# Actuator-MKI-2.net
KiCad netlist of a schematic drawn in EAGLE
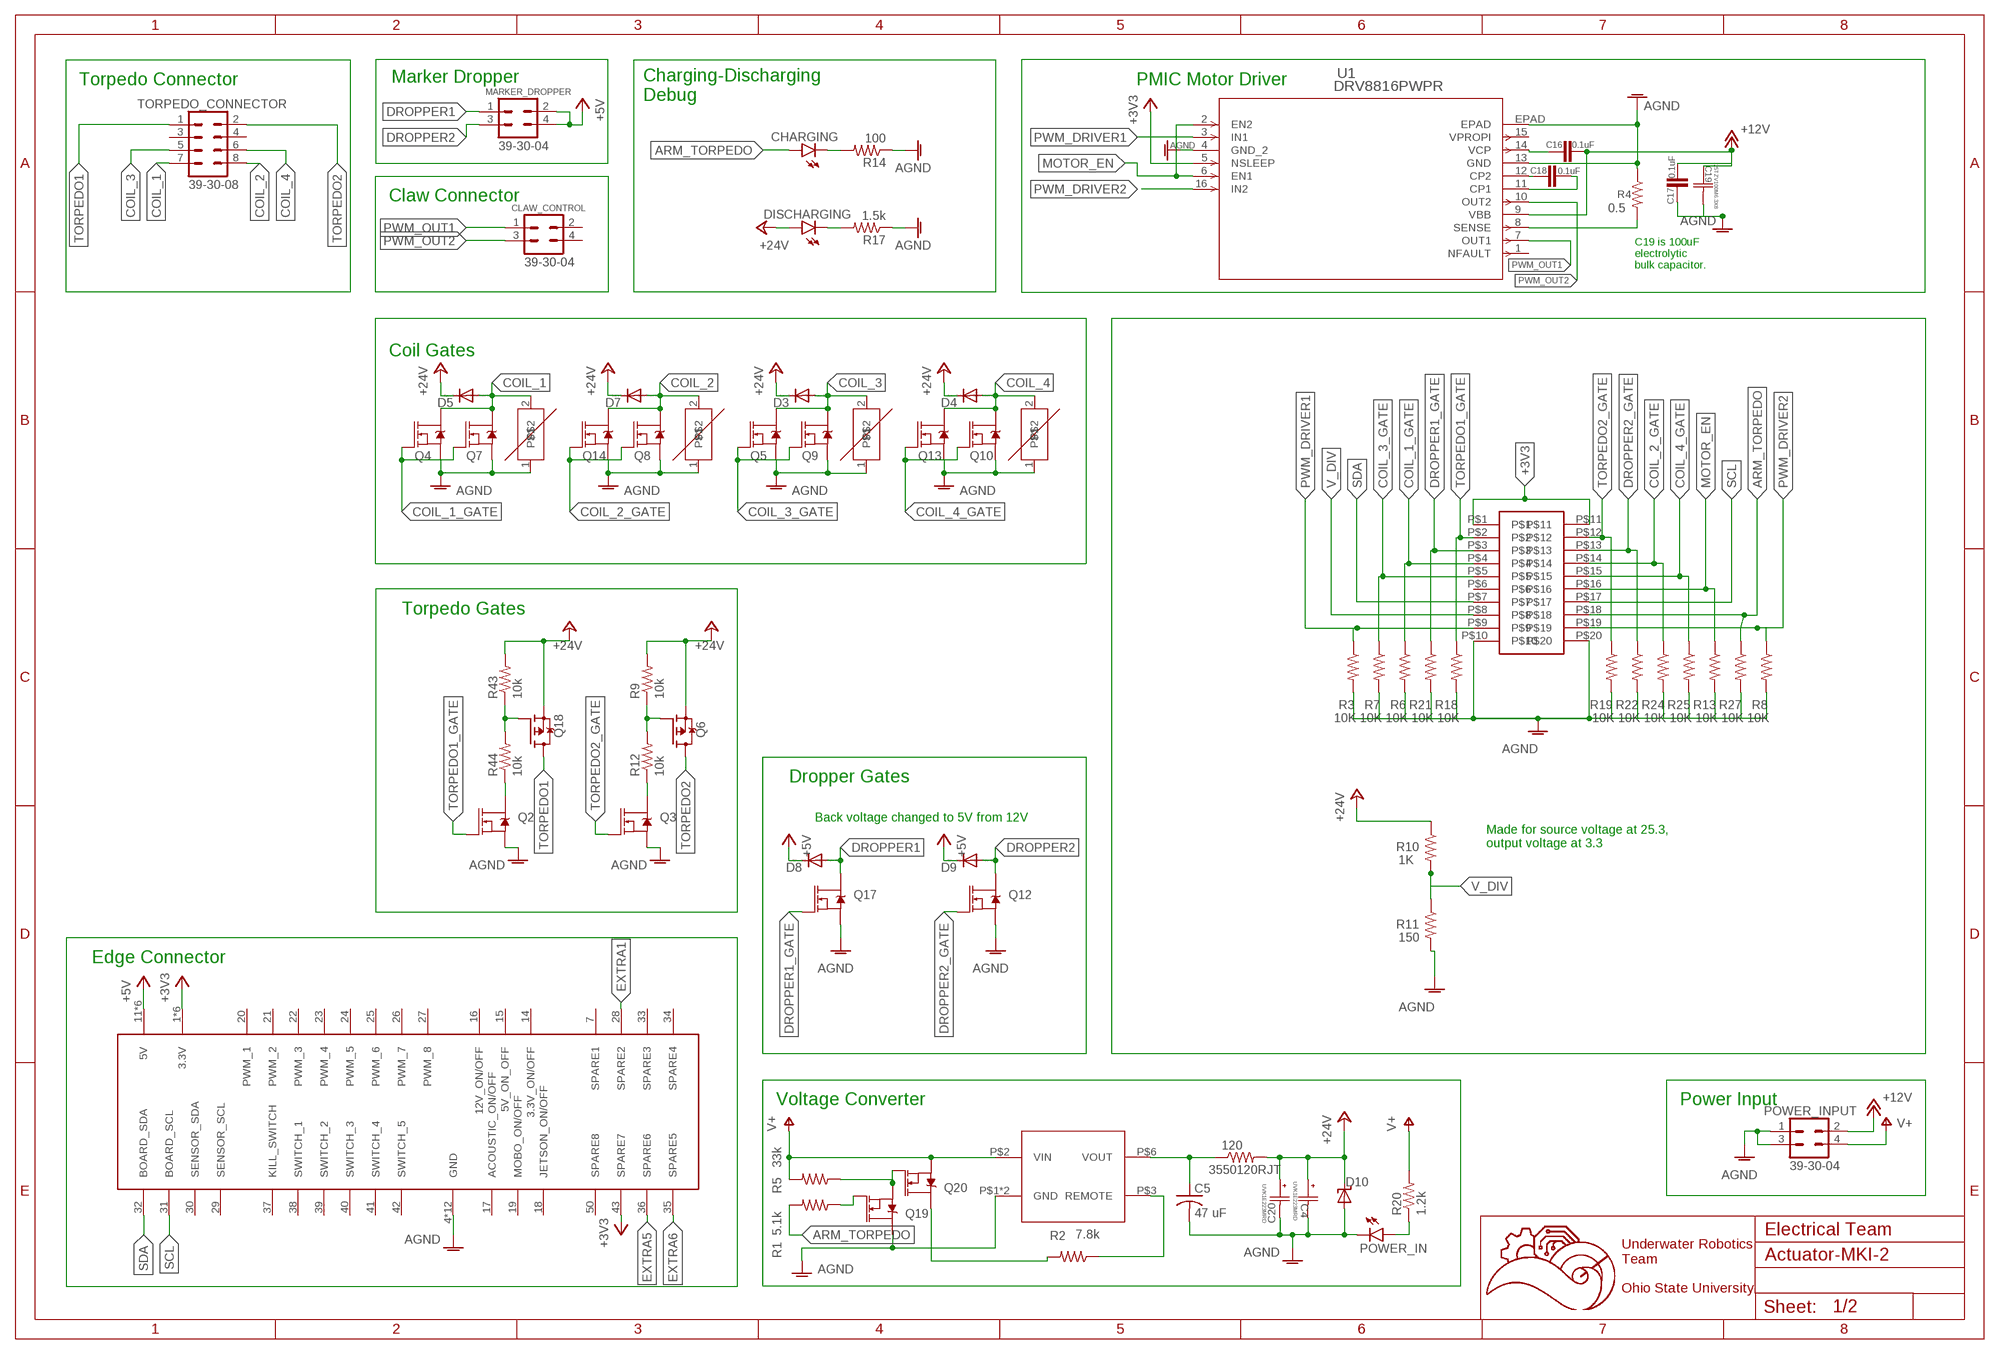
[diagram p0: schematic, sheet 1]
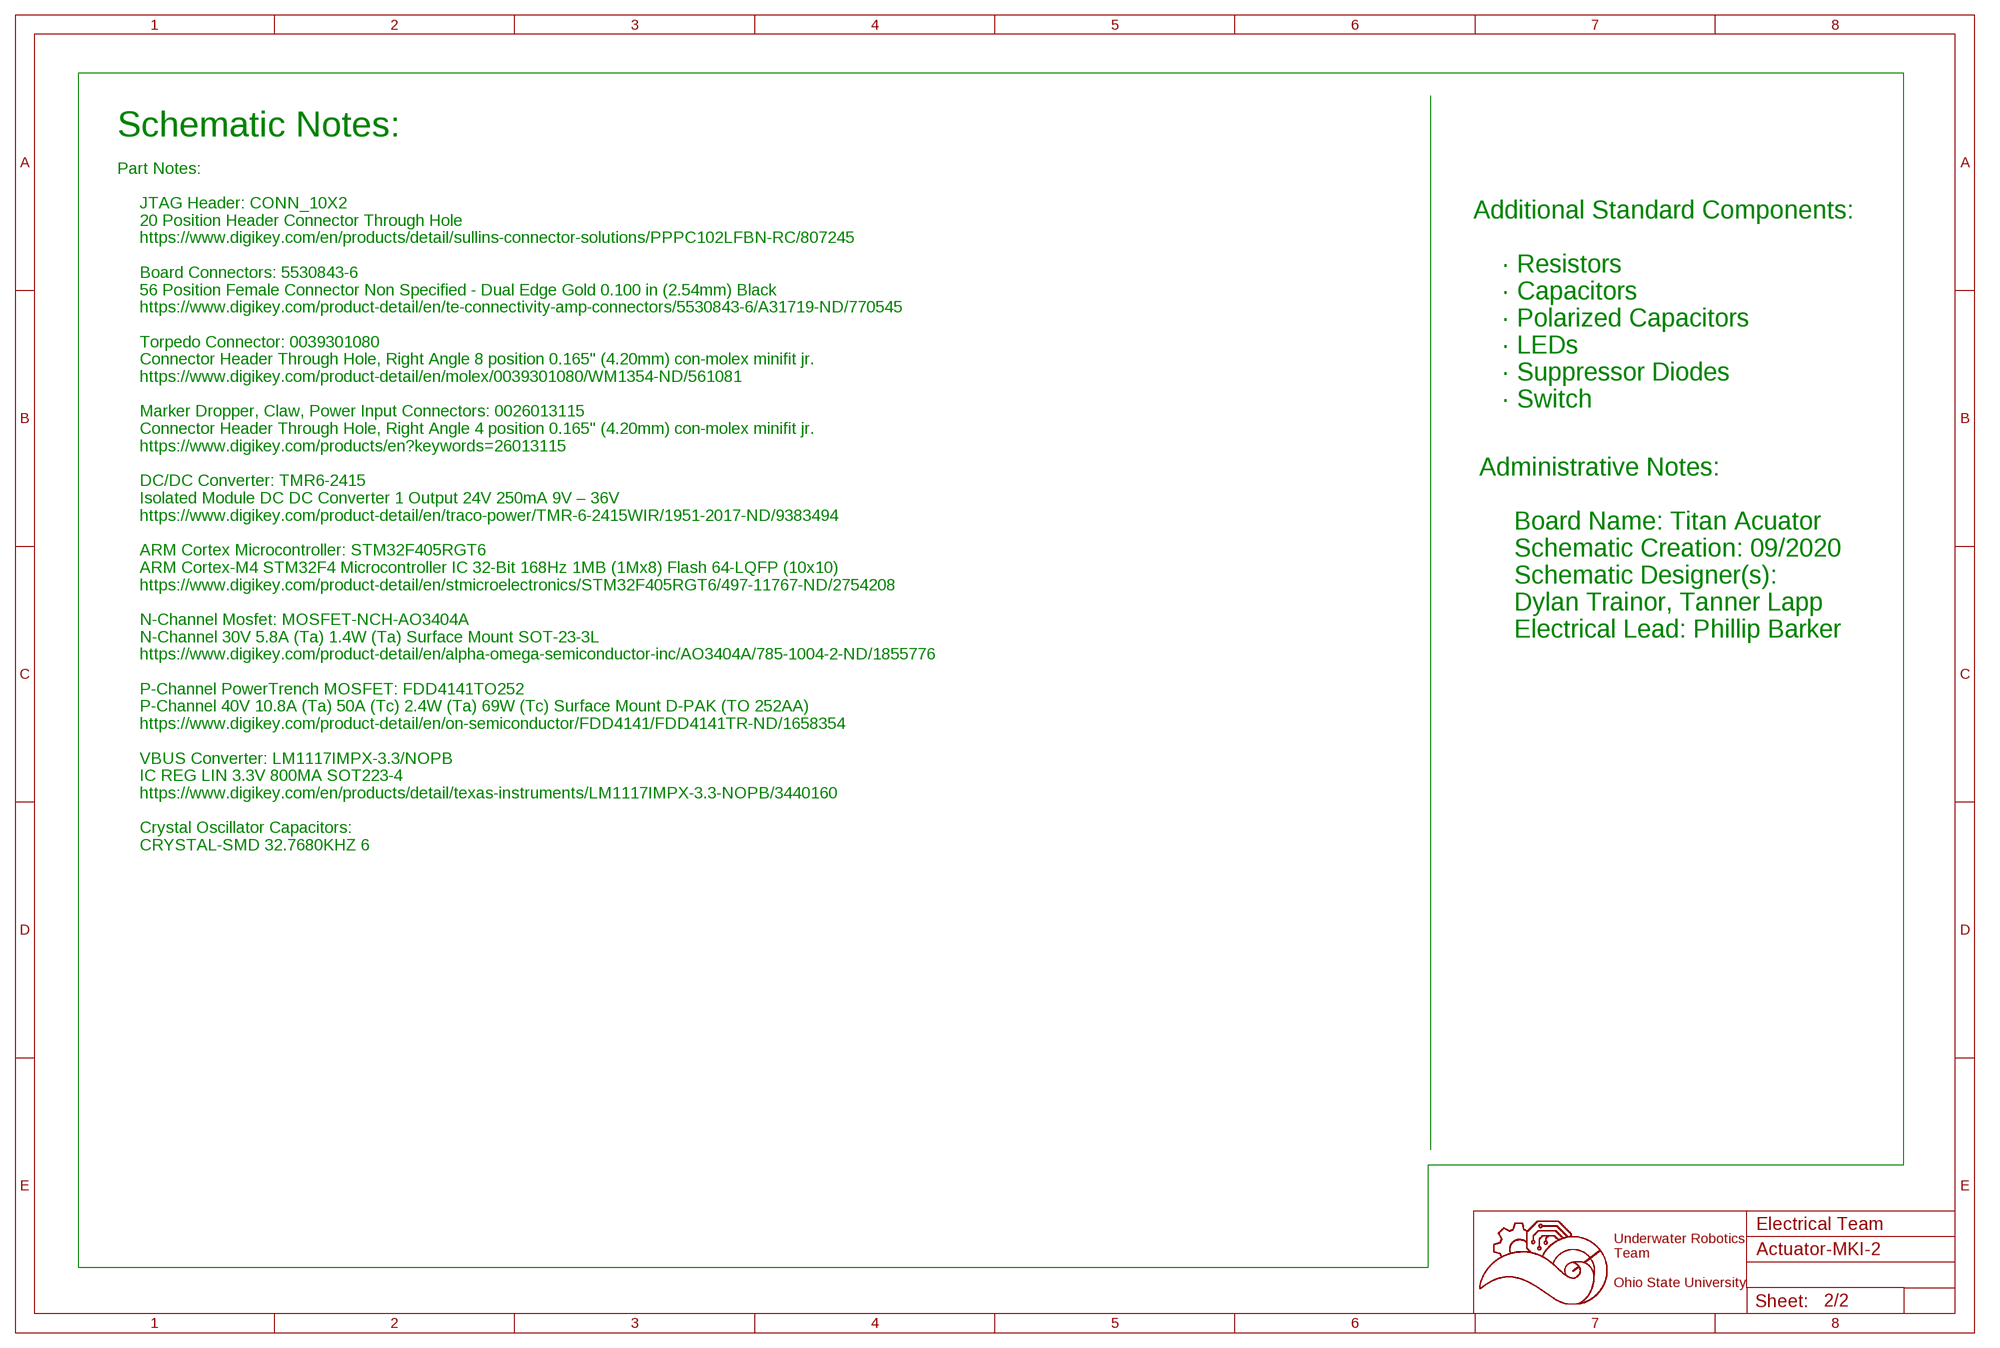
[diagram p1: schematic, sheet 2]

(export (version "E")
  (design (tool "Eeschema 10.0.6"))
  (components
    (comp (ref "120")
      (value "3550120RJT")
      (footprint "eagle-import:3550120RJT")
      (libsource (lib "eagle-import") (part "3550120RJT"))
    )
    (comp (ref "C4")
      (value "UVK1E223MRD")
      (footprint "eagle-import:CAP_UFW_25X50_NCH")
      (fields (field (name "COPYRIGHT") "Copyright (C) 2018 Accelerated Designs. All rights reserved"))
      (libsource (lib "eagle-import") (part "UVK1E223MRD"))
    )
    (comp (ref "C5")
      (value "47 uF")
      (footprint "eagle-import:C1206K")
      (libsource (lib "eagle-import") (part "C-USC1206K"))
    )
    (comp (ref "C16")
      (value "0.1uF")
      (footprint "eagle-import:C0603")
      (libsource (lib "eagle-import") (part "C-EUC0603"))
    )
    (comp (ref "C17")
      (value "0.1uF")
      (footprint "eagle-import:C0603")
      (libsource (lib "eagle-import") (part "C-EUC0603"))
    )
    (comp (ref "C18")
      (value "0.1uF")
      (footprint "eagle-import:C0603")
      (libsource (lib "eagle-import") (part "C-EUC0603"))
    )
    (comp (ref "C19")
      (value "25TZV100M6.3X8")
      (footprint "eagle-import:CAP_J-V_6P3X8_RUB")
      (fields (field (name "COPYRIGHT") "Copyright (C) 2018 Accelerated Designs. All rights reserved"))
      (libsource (lib "eagle-import") (part "25TZV100M6.3X8"))
    )
    (comp (ref "C20")
      (value "UVK1E223MRD")
      (footprint "eagle-import:CAP_UFW_25X50_NCH")
      (fields (field (name "COPYRIGHT") "Copyright (C) 2018 Accelerated Designs. All rights reserved"))
      (libsource (lib "eagle-import") (part "UVK1E223MRD"))
    )
    (comp (ref "CHARGING")
      (value "LEDCHIPLED_0603")
      (footprint "eagle-import:CHIPLED_0603")
      (libsource (lib "eagle-import") (part "LEDCHIPLED_0603"))
    )
    (comp (ref "CLAW_CONTROL")
      (value "39-30-04")
      (footprint "eagle-import:39-30-_04_")
      (libsource (lib "eagle-import") (part "39-30-?04?"))
    )
    (comp (ref "D3")
      (value "DIODE-SMB")
      (footprint "eagle-import:SMB")
      (libsource (lib "eagle-import") (part "DIODE-SMB"))
    )
    (comp (ref "D4")
      (value "DIODE-SMB")
      (footprint "eagle-import:SMB")
      (libsource (lib "eagle-import") (part "DIODE-SMB"))
    )
    (comp (ref "D5")
      (value "DIODE-SMB")
      (footprint "eagle-import:SMB")
      (libsource (lib "eagle-import") (part "DIODE-SMB"))
    )
    (comp (ref "D7")
      (value "DIODE-SMB")
      (footprint "eagle-import:SMB")
      (libsource (lib "eagle-import") (part "DIODE-SMB"))
    )
    (comp (ref "D8")
      (value "DIODE-SMB")
      (footprint "eagle-import:SMB")
      (libsource (lib "eagle-import") (part "DIODE-SMB"))
    )
    (comp (ref "D9")
      (value "DIODE-SMB")
      (footprint "eagle-import:SMB")
      (libsource (lib "eagle-import") (part "DIODE-SMB"))
    )
    (comp (ref "D10")
      (value "SUPPRESSOR-SMBJ")
      (footprint "eagle-import:SMBJ")
      (libsource (lib "eagle-import") (part "SUPPRESSOR-SMBJ"))
    )
    (comp (ref "DISCHARGING")
      (value "LEDCHIPLED_0603")
      (footprint "eagle-import:CHIPLED_0603")
      (libsource (lib "eagle-import") (part "LEDCHIPLED_0603"))
    )
    (comp (ref "MARKER_DROPPER")
      (value "39-30-04")
      (footprint "eagle-import:39-30-_04_")
      (libsource (lib "eagle-import") (part "39-30-?04?"))
    )
    (comp (ref "POWER_IN")
      (value "LEDCHIPLED_0603")
      (footprint "eagle-import:CHIPLED_0603")
      (libsource (lib "eagle-import") (part "LEDCHIPLED_0603"))
    )
    (comp (ref "POWER_INPUT")
      (value "39-30-04")
      (footprint "eagle-import:39-30-_04_")
      (libsource (lib "eagle-import") (part "39-30-?04?"))
    )
    (comp (ref "Q2")
      (value "MOSFET-NCH-AO3404A")
      (footprint "eagle-import:SOT23-3")
      (libsource (lib "eagle-import") (part "MOSFET-NCH-AO3404A"))
    )
    (comp (ref "Q3")
      (value "MOSFET-NCH-AO3404A")
      (footprint "eagle-import:SOT23-3")
      (libsource (lib "eagle-import") (part "MOSFET-NCH-AO3404A"))
    )
    (comp (ref "Q4")
      (value "MOSFET-NCH-AO3404A")
      (footprint "eagle-import:SOT23-3")
      (libsource (lib "eagle-import") (part "MOSFET-NCH-AO3404A"))
    )
    (comp (ref "Q5")
      (value "MOSFET-NCH-AO3404A")
      (footprint "eagle-import:SOT23-3")
      (libsource (lib "eagle-import") (part "MOSFET-NCH-AO3404A"))
    )
    (comp (ref "Q6")
      (value "FDD4141TO252")
      (footprint "eagle-import:TO252")
      (libsource (lib "eagle-import") (part "FDD4141TO252"))
    )
    (comp (ref "Q7")
      (value "MOSFET-NCH-AO3404A")
      (footprint "eagle-import:SOT23-3")
      (libsource (lib "eagle-import") (part "MOSFET-NCH-AO3404A"))
    )
    (comp (ref "Q8")
      (value "MOSFET-NCH-AO3404A")
      (footprint "eagle-import:SOT23-3")
      (libsource (lib "eagle-import") (part "MOSFET-NCH-AO3404A"))
    )
    (comp (ref "Q9")
      (value "MOSFET-NCH-AO3404A")
      (footprint "eagle-import:SOT23-3")
      (libsource (lib "eagle-import") (part "MOSFET-NCH-AO3404A"))
    )
    (comp (ref "Q10")
      (value "MOSFET-NCH-AO3404A")
      (footprint "eagle-import:SOT23-3")
      (libsource (lib "eagle-import") (part "MOSFET-NCH-AO3404A"))
    )
    (comp (ref "Q12")
      (value "MOSFET-NCH-AO3404A")
      (footprint "eagle-import:SOT23-3")
      (libsource (lib "eagle-import") (part "MOSFET-NCH-AO3404A"))
    )
    (comp (ref "Q13")
      (value "MOSFET-NCH-AO3404A")
      (footprint "eagle-import:SOT23-3")
      (libsource (lib "eagle-import") (part "MOSFET-NCH-AO3404A"))
    )
    (comp (ref "Q14")
      (value "MOSFET-NCH-AO3404A")
      (footprint "eagle-import:SOT23-3")
      (libsource (lib "eagle-import") (part "MOSFET-NCH-AO3404A"))
    )
    (comp (ref "Q17")
      (value "MOSFET-NCH-AO3404A")
      (footprint "eagle-import:SOT23-3")
      (libsource (lib "eagle-import") (part "MOSFET-NCH-AO3404A"))
    )
    (comp (ref "Q18")
      (value "FDD4141TO252")
      (footprint "eagle-import:TO252")
      (libsource (lib "eagle-import") (part "FDD4141TO252"))
    )
    (comp (ref "Q19")
      (value "MOSFET-NCH-AO3404A")
      (footprint "eagle-import:SOT23-3")
      (libsource (lib "eagle-import") (part "MOSFET-NCH-AO3404A"))
    )
    (comp (ref "Q20")
      (value "MOSFET-NCH-AO3404A")
      (footprint "eagle-import:SOT23-3")
      (libsource (lib "eagle-import") (part "MOSFET-NCH-AO3404A"))
    )
    (comp (ref "R1")
      (value "5.1k")
      (footprint "eagle-import:R0603")
      (libsource (lib "eagle-import") (part "R-US_R0603"))
    )
    (comp (ref "R2")
      (value "7.8k")
      (footprint "eagle-import:R0603")
      (libsource (lib "eagle-import") (part "R-US_R0603"))
    )
    (comp (ref "R3")
      (value "10K")
      (footprint "eagle-import:R0603")
      (libsource (lib "eagle-import") (part "R-US_R0603"))
    )
    (comp (ref "R4")
      (value "0.5")
      (footprint "eagle-import:R0805")
      (libsource (lib "eagle-import") (part "R-US_R0805"))
    )
    (comp (ref "R5")
      (value "33k")
      (footprint "eagle-import:R0603")
      (libsource (lib "eagle-import") (part "R-US_R0603"))
    )
    (comp (ref "R6")
      (value "10K")
      (footprint "eagle-import:R0603")
      (libsource (lib "eagle-import") (part "R-US_R0603"))
    )
    (comp (ref "R7")
      (value "10K")
      (footprint "eagle-import:R0603")
      (libsource (lib "eagle-import") (part "R-US_R0603"))
    )
    (comp (ref "R8")
      (value "10K")
      (footprint "eagle-import:R0603")
      (libsource (lib "eagle-import") (part "R-US_R0603"))
    )
    (comp (ref "R9")
      (value "10k")
      (footprint "eagle-import:R0603")
      (libsource (lib "eagle-import") (part "R-US_R0603"))
    )
    (comp (ref "R10")
      (value "1K")
      (footprint "eagle-import:R0603")
      (libsource (lib "eagle-import") (part "R-US_R0603"))
    )
    (comp (ref "R11")
      (value "150")
      (footprint "eagle-import:R0603")
      (libsource (lib "eagle-import") (part "R-US_R0603"))
    )
    (comp (ref "R12")
      (value "10k")
      (footprint "eagle-import:R0603")
      (libsource (lib "eagle-import") (part "R-US_R0603"))
    )
    (comp (ref "R13")
      (value "10K")
      (footprint "eagle-import:R0603")
      (libsource (lib "eagle-import") (part "R-US_R0603"))
    )
    (comp (ref "R14")
      (value "100")
      (footprint "eagle-import:R0805")
      (libsource (lib "eagle-import") (part "R-US_R0805"))
    )
    (comp (ref "R17")
      (value "1.5k")
      (footprint "eagle-import:R0805")
      (libsource (lib "eagle-import") (part "R-US_R0805"))
    )
    (comp (ref "R18")
      (value "10K")
      (footprint "eagle-import:R0603")
      (libsource (lib "eagle-import") (part "R-US_R0603"))
    )
    (comp (ref "R19")
      (value "10K")
      (footprint "eagle-import:R0603")
      (libsource (lib "eagle-import") (part "R-US_R0603"))
    )
    (comp (ref "R20")
      (value "1.2k")
      (footprint "eagle-import:R0805")
      (libsource (lib "eagle-import") (part "R-US_R0805"))
    )
    (comp (ref "R21")
      (value "10K")
      (footprint "eagle-import:R0603")
      (libsource (lib "eagle-import") (part "R-US_R0603"))
    )
    (comp (ref "R22")
      (value "10K")
      (footprint "eagle-import:R0603")
      (libsource (lib "eagle-import") (part "R-US_R0603"))
    )
    (comp (ref "R24")
      (value "10K")
      (footprint "eagle-import:R0603")
      (libsource (lib "eagle-import") (part "R-US_R0603"))
    )
    (comp (ref "R25")
      (value "10K")
      (footprint "eagle-import:R0603")
      (libsource (lib "eagle-import") (part "R-US_R0603"))
    )
    (comp (ref "R27")
      (value "10K")
      (footprint "eagle-import:R0603")
      (libsource (lib "eagle-import") (part "R-US_R0603"))
    )
    (comp (ref "R43")
      (value "10k")
      (footprint "eagle-import:R0603")
      (libsource (lib "eagle-import") (part "R-US_R0603"))
    )
    (comp (ref "R44")
      (value "10k")
      (footprint "eagle-import:R0603")
      (libsource (lib "eagle-import") (part "R-US_R0603"))
    )
    (comp (ref "TORPEDO_CONNECTOR")
      (value "39-30-08")
      (footprint "eagle-import:39-30-_08_")
      (libsource (lib "eagle-import") (part "39-30-?08?"))
    )
    (comp (ref "U$1")
      (value "5530843-EDGE")
      (footprint "eagle-import:5530843-6-BOARDFINGERS")
      (libsource (lib "eagle-import") (part "5530843-EDGE"))
    )
    (comp (ref "U$4")
      (value "ERZ-VF2M270ERZ-VF2M270")
      (footprint "eagle-import:RESM8060X320N")
      (libsource (lib "eagle-import") (part "ERZ-VF2M270ERZ-VF2M270"))
    )
    (comp (ref "U$5")
      (value "ERZ-VF2M270ERZ-VF2M270")
      (footprint "eagle-import:RESM8060X320N")
      (libsource (lib "eagle-import") (part "ERZ-VF2M270ERZ-VF2M270"))
    )
    (comp (ref "U$6")
      (value "TMR6-2415")
      (footprint "eagle-import:TMR6-2415")
      (libsource (lib "eagle-import") (part "TMR6-2415"))
    )
    (comp (ref "U$7")
      (value "ERZ-VF2M270ERZ-VF2M270")
      (footprint "eagle-import:RESM8060X320N")
      (libsource (lib "eagle-import") (part "ERZ-VF2M270ERZ-VF2M270"))
    )
    (comp (ref "U$8")
      (value "ERZ-VF2M270ERZ-VF2M270")
      (footprint "eagle-import:RESM8060X320N")
      (libsource (lib "eagle-import") (part "ERZ-VF2M270ERZ-VF2M270"))
    )
    (comp (ref "U$9")
      (value "JTAG-SMD")
      (footprint "eagle-import:JTAG-SMD")
      (libsource (lib "eagle-import") (part "JTAG-SMD"))
    )
    (comp (ref "U1")
      (value "DRV8816PWPR")
      (footprint "eagle-import:PWP_16")
      (libsource (lib "eagle-import") (part "DRV8816PWPR"))
    )
  )
  (nets
    (net (code "1") (name "+3V3") (class "Default")
      (node (ref "U$1") (pin "1") (pinfunction "3.3V_1") (pintype "bidirectional"))
      (node (ref "U$1") (pin "2") (pinfunction "3.3V_2") (pintype "bidirectional"))
      (node (ref "U$1") (pin "3") (pinfunction "3.3V_3") (pintype "bidirectional"))
      (node (ref "U$1") (pin "43") (pinfunction "SPARE7_43") (pintype "bidirectional"))
      (node (ref "U$1") (pin "54") (pinfunction "3.3V_54") (pintype "bidirectional"))
      (node (ref "U$1") (pin "55") (pinfunction "3.3V_55") (pintype "bidirectional"))
      (node (ref "U$1") (pin "56") (pinfunction "3.3V_56") (pintype "bidirectional"))
      (node (ref "U$9") (pin "P$1") (pinfunction "P$1_P$1") (pintype "bidirectional"))
      (node (ref "U$9") (pin "P$11") (pinfunction "P$11_P$11") (pintype "bidirectional"))
      (node (ref "U1") (pin "5") (pinfunction "NSLEEP_5") (pintype "input"))
    )
    (net (code "2") (name "+5V") (class "Default")
      (node (ref "D8") (pin "C") (pinfunction "C_C") (pintype "passive"))
      (node (ref "D9") (pin "C") (pinfunction "C_C") (pintype "passive"))
      (node (ref "MARKER_DROPPER") (pin "2") (pinfunction "2_2") (pintype "passive"))
      (node (ref "MARKER_DROPPER") (pin "4") (pinfunction "4_4") (pintype "passive"))
      (node (ref "U$1") (pin "11") (pinfunction "5V_11") (pintype "bidirectional"))
      (node (ref "U$1") (pin "12") (pinfunction "5V_12") (pintype "bidirectional"))
      (node (ref "U$1") (pin "13") (pinfunction "5V_13") (pintype "bidirectional"))
      (node (ref "U$1") (pin "44") (pinfunction "5V_44") (pintype "bidirectional"))
      (node (ref "U$1") (pin "45") (pinfunction "5V_45") (pintype "bidirectional"))
      (node (ref "U$1") (pin "46") (pinfunction "5V_46") (pintype "bidirectional"))
    )
    (net (code "3") (name "+12V") (class "Default")
      (node (ref "C16") (pin "2") (pinfunction "2_2") (pintype "passive"))
      (node (ref "C17") (pin "2") (pinfunction "2_2") (pintype "passive"))
      (node (ref "C19") (pin "1") (pinfunction "1_1") (pintype "passive"))
      (node (ref "POWER_INPUT") (pin "2") (pinfunction "2_2") (pintype "passive"))
      (node (ref "U1") (pin "9") (pinfunction "VBB_9") (pintype "power_in"))
    )
    (net (code "4") (name "+24V") (class "Default")
      (node (ref "120") (pin "P$2") (pinfunction "2_P$2") (pintype "passive"))
      (node (ref "C20") (pin "1") (pinfunction "1_1") (pintype "passive"))
      (node (ref "C4") (pin "1") (pinfunction "1_1") (pintype "passive"))
      (node (ref "D10") (pin "C") (pinfunction "C_C") (pintype "passive"))
      (node (ref "D3") (pin "C") (pinfunction "C_C") (pintype "passive"))
      (node (ref "D4") (pin "C") (pinfunction "C_C") (pintype "passive"))
      (node (ref "D5") (pin "C") (pinfunction "C_C") (pintype "passive"))
      (node (ref "D7") (pin "C") (pinfunction "C_C") (pintype "passive"))
      (node (ref "DISCHARGING") (pin "A") (pinfunction "A_A") (pintype "passive"))
      (node (ref "Q18") (pin "2") (pinfunction "S_2") (pintype "passive"))
      (node (ref "Q6") (pin "2") (pinfunction "S_2") (pintype "passive"))
      (node (ref "R10") (pin "1") (pinfunction "1_1") (pintype "passive"))
      (node (ref "R43") (pin "2") (pinfunction "2_2") (pintype "passive"))
      (node (ref "R9") (pin "2") (pinfunction "2_2") (pintype "passive"))
    )
    (net (code "5") (name "AGND") (class "Default")
      (node (ref "C17") (pin "1") (pinfunction "1_1") (pintype "passive"))
      (node (ref "C19") (pin "2") (pinfunction "2_2") (pintype "passive"))
      (node (ref "C20") (pin "2") (pinfunction "2_2") (pintype "passive"))
      (node (ref "C4") (pin "2") (pinfunction "2_2") (pintype "passive"))
      (node (ref "C5") (pin "2") (pinfunction "2_2") (pintype "passive"))
      (node (ref "D10") (pin "A") (pinfunction "A_A") (pintype "passive"))
      (node (ref "POWER_IN") (pin "C") (pinfunction "C_C") (pintype "passive"))
      (node (ref "POWER_INPUT") (pin "1") (pinfunction "1_1") (pintype "passive"))
      (node (ref "POWER_INPUT") (pin "3") (pinfunction "3_3") (pintype "passive"))
      (node (ref "Q10") (pin "2") (pinfunction "S_2") (pintype "bidirectional"))
      (node (ref "Q12") (pin "2") (pinfunction "S_2") (pintype "bidirectional"))
      (node (ref "Q13") (pin "2") (pinfunction "S_2") (pintype "bidirectional"))
      (node (ref "Q14") (pin "2") (pinfunction "S_2") (pintype "bidirectional"))
      (node (ref "Q17") (pin "2") (pinfunction "S_2") (pintype "bidirectional"))
      (node (ref "Q19") (pin "3") (pinfunction "D_3") (pintype "bidirectional"))
      (node (ref "Q2") (pin "2") (pinfunction "S_2") (pintype "bidirectional"))
      (node (ref "Q3") (pin "2") (pinfunction "S_2") (pintype "bidirectional"))
      (node (ref "Q4") (pin "2") (pinfunction "S_2") (pintype "bidirectional"))
      (node (ref "Q5") (pin "2") (pinfunction "S_2") (pintype "bidirectional"))
      (node (ref "Q7") (pin "2") (pinfunction "S_2") (pintype "bidirectional"))
      (node (ref "Q8") (pin "2") (pinfunction "S_2") (pintype "bidirectional"))
      (node (ref "Q9") (pin "2") (pinfunction "S_2") (pintype "bidirectional"))
      (node (ref "R11") (pin "2") (pinfunction "2_2") (pintype "passive"))
      (node (ref "R13") (pin "2") (pinfunction "2_2") (pintype "passive"))
      (node (ref "R14") (pin "1") (pinfunction "1_1") (pintype "passive"))
      (node (ref "R17") (pin "1") (pinfunction "1_1") (pintype "passive"))
      (node (ref "R18") (pin "2") (pinfunction "2_2") (pintype "passive"))
      (node (ref "R19") (pin "2") (pinfunction "2_2") (pintype "passive"))
      (node (ref "R21") (pin "2") (pinfunction "2_2") (pintype "passive"))
      (node (ref "R22") (pin "2") (pinfunction "2_2") (pintype "passive"))
      (node (ref "R24") (pin "2") (pinfunction "2_2") (pintype "passive"))
      (node (ref "R25") (pin "2") (pinfunction "2_2") (pintype "passive"))
      (node (ref "R27") (pin "2") (pinfunction "2_2") (pintype "passive"))
      (node (ref "R3") (pin "2") (pinfunction "2_2") (pintype "passive"))
      (node (ref "R4") (pin "1") (pinfunction "1_1") (pintype "passive"))
      (node (ref "R6") (pin "2") (pinfunction "2_2") (pintype "passive"))
      (node (ref "R7") (pin "2") (pinfunction "2_2") (pintype "passive"))
      (node (ref "R8") (pin "2") (pinfunction "2_2") (pintype "passive"))
      (node (ref "U$1") (pin "10") (pinfunction "GND_10") (pintype "bidirectional"))
      (node (ref "U$1") (pin "4") (pinfunction "GND_4") (pintype "bidirectional"))
      (node (ref "U$1") (pin "47") (pinfunction "GND_47") (pintype "bidirectional"))
      (node (ref "U$1") (pin "48") (pinfunction "GND_48") (pintype "bidirectional"))
      (node (ref "U$1") (pin "49") (pinfunction "GND_49") (pintype "bidirectional"))
      (node (ref "U$1") (pin "5") (pinfunction "GND_5") (pintype "bidirectional"))
      (node (ref "U$1") (pin "51") (pinfunction "GND_51") (pintype "bidirectional"))
      (node (ref "U$1") (pin "52") (pinfunction "GND_52") (pintype "bidirectional"))
      (node (ref "U$1") (pin "53") (pinfunction "GND_53") (pintype "bidirectional"))
      (node (ref "U$1") (pin "6") (pinfunction "GND_6") (pintype "bidirectional"))
      (node (ref "U$1") (pin "8") (pinfunction "GND_8") (pintype "bidirectional"))
      (node (ref "U$1") (pin "9") (pinfunction "GND_9") (pintype "bidirectional"))
      (node (ref "U$4") (pin "1") (pinfunction "P$1_1") (pintype "bidirectional"))
      (node (ref "U$5") (pin "1") (pinfunction "P$1_1") (pintype "bidirectional"))
      (node (ref "U$6") (pin "P$1") (pinfunction "GND_P$1") (pintype "bidirectional"))
      (node (ref "U$6") (pin "P$7") (pinfunction "GND_P$7") (pintype "bidirectional"))
      (node (ref "U$7") (pin "1") (pinfunction "P$1_1") (pintype "bidirectional"))
      (node (ref "U$8") (pin "1") (pinfunction "P$1_1") (pintype "bidirectional"))
      (node (ref "U$9") (pin "P$10") (pinfunction "P$10_P$10") (pintype "bidirectional"))
      (node (ref "U$9") (pin "P$20") (pinfunction "P$20_P$20") (pintype "bidirectional"))
      (node (ref "U1") (pin "13") (pinfunction "GND_13") (pintype "power_in"))
      (node (ref "U1") (pin "4") (pinfunction "GND_2_4") (pintype "power_in"))
      (node (ref "U1") (pin "EPAD") (pinfunction "EPAD_EPAD") (pintype "passive"))
    )
    (net (code "6") (name "ARM_TORPEDO") (class "Default")
      (node (ref "CHARGING") (pin "A") (pinfunction "A_A") (pintype "passive"))
      (node (ref "R1") (pin "2") (pinfunction "2_2") (pintype "passive"))
      (node (ref "R27") (pin "1") (pinfunction "1_1") (pintype "passive"))
      (node (ref "U$9") (pin "P$18") (pinfunction "P$18_P$18") (pintype "bidirectional"))
    )
    (net (code "7") (name "COIL_1") (class "Default")
      (node (ref "D5") (pin "A") (pinfunction "A_A") (pintype "passive"))
      (node (ref "Q4") (pin "3") (pinfunction "D_3") (pintype "bidirectional"))
      (node (ref "Q7") (pin "3") (pinfunction "D_3") (pintype "bidirectional"))
      (node (ref "TORPEDO_CONNECTOR") (pin "7") (pinfunction "7_7") (pintype "passive"))
      (node (ref "U$8") (pin "2") (pinfunction "P$2_2") (pintype "bidirectional"))
    )
    (net (code "8") (name "COIL_1_GATE") (class "Default")
      (node (ref "Q4") (pin "1") (pinfunction "G_1") (pintype "bidirectional"))
      (node (ref "Q7") (pin "1") (pinfunction "G_1") (pintype "bidirectional"))
      (node (ref "R6") (pin "1") (pinfunction "1_1") (pintype "passive"))
      (node (ref "U$9") (pin "P$4") (pinfunction "P$4_P$4") (pintype "bidirectional"))
    )
    (net (code "9") (name "COIL_2") (class "Default")
      (node (ref "D7") (pin "A") (pinfunction "A_A") (pintype "passive"))
      (node (ref "Q14") (pin "3") (pinfunction "D_3") (pintype "bidirectional"))
      (node (ref "Q8") (pin "3") (pinfunction "D_3") (pintype "bidirectional"))
      (node (ref "TORPEDO_CONNECTOR") (pin "8") (pinfunction "8_8") (pintype "passive"))
      (node (ref "U$7") (pin "2") (pinfunction "P$2_2") (pintype "bidirectional"))
    )
    (net (code "10") (name "COIL_2_GATE") (class "Default")
      (node (ref "Q14") (pin "1") (pinfunction "G_1") (pintype "bidirectional"))
      (node (ref "Q8") (pin "1") (pinfunction "G_1") (pintype "bidirectional"))
      (node (ref "R24") (pin "1") (pinfunction "1_1") (pintype "passive"))
      (node (ref "U$9") (pin "P$14") (pinfunction "P$14_P$14") (pintype "bidirectional"))
    )
    (net (code "11") (name "COIL_3") (class "Default")
      (node (ref "D3") (pin "A") (pinfunction "A_A") (pintype "passive"))
      (node (ref "Q5") (pin "3") (pinfunction "D_3") (pintype "bidirectional"))
      (node (ref "Q9") (pin "3") (pinfunction "D_3") (pintype "bidirectional"))
      (node (ref "TORPEDO_CONNECTOR") (pin "5") (pinfunction "5_5") (pintype "passive"))
      (node (ref "U$5") (pin "2") (pinfunction "P$2_2") (pintype "bidirectional"))
    )
    (net (code "12") (name "COIL_3_GATE") (class "Default")
      (node (ref "Q5") (pin "1") (pinfunction "G_1") (pintype "bidirectional"))
      (node (ref "Q9") (pin "1") (pinfunction "G_1") (pintype "bidirectional"))
      (node (ref "R7") (pin "1") (pinfunction "1_1") (pintype "passive"))
      (node (ref "U$9") (pin "P$5") (pinfunction "P$5_P$5") (pintype "bidirectional"))
    )
    (net (code "13") (name "COIL_4") (class "Default")
      (node (ref "D4") (pin "A") (pinfunction "A_A") (pintype "passive"))
      (node (ref "Q10") (pin "3") (pinfunction "D_3") (pintype "bidirectional"))
      (node (ref "Q13") (pin "3") (pinfunction "D_3") (pintype "bidirectional"))
      (node (ref "TORPEDO_CONNECTOR") (pin "6") (pinfunction "6_6") (pintype "passive"))
      (node (ref "U$4") (pin "2") (pinfunction "P$2_2") (pintype "bidirectional"))
    )
    (net (code "14") (name "COIL_4_GATE") (class "Default")
      (node (ref "Q10") (pin "1") (pinfunction "G_1") (pintype "bidirectional"))
      (node (ref "Q13") (pin "1") (pinfunction "G_1") (pintype "bidirectional"))
      (node (ref "R25") (pin "1") (pinfunction "1_1") (pintype "passive"))
      (node (ref "U$9") (pin "P$15") (pinfunction "P$15_P$15") (pintype "bidirectional"))
    )
    (net (code "15") (name "DROPPER1") (class "Default")
      (node (ref "D8") (pin "A") (pinfunction "A_A") (pintype "passive"))
      (node (ref "MARKER_DROPPER") (pin "1") (pinfunction "1_1") (pintype "passive"))
      (node (ref "Q17") (pin "3") (pinfunction "D_3") (pintype "bidirectional"))
    )
    (net (code "16") (name "DROPPER1_GATE") (class "Default")
      (node (ref "Q17") (pin "1") (pinfunction "G_1") (pintype "bidirectional"))
      (node (ref "R21") (pin "1") (pinfunction "1_1") (pintype "passive"))
      (node (ref "U$9") (pin "P$3") (pinfunction "P$3_P$3") (pintype "bidirectional"))
    )
    (net (code "17") (name "DROPPER2") (class "Default")
      (node (ref "D9") (pin "A") (pinfunction "A_A") (pintype "passive"))
      (node (ref "MARKER_DROPPER") (pin "3") (pinfunction "3_3") (pintype "passive"))
      (node (ref "Q12") (pin "3") (pinfunction "D_3") (pintype "bidirectional"))
    )
    (net (code "18") (name "DROPPER2_GATE") (class "Default")
      (node (ref "Q12") (pin "1") (pinfunction "G_1") (pintype "bidirectional"))
      (node (ref "R22") (pin "1") (pinfunction "1_1") (pintype "passive"))
      (node (ref "U$9") (pin "P$13") (pinfunction "P$13_P$13") (pintype "bidirectional"))
    )
    (net (code "19") (name "EXTRA1") (class "Default")
      (node (ref "U$1") (pin "28") (pinfunction "SPARE2_28") (pintype "bidirectional"))
    )
    (net (code "20") (name "EXTRA5") (class "Default")
      (node (ref "U$1") (pin "36") (pinfunction "SPARE6_36") (pintype "bidirectional"))
    )
    (net (code "21") (name "EXTRA6") (class "Default")
      (node (ref "U$1") (pin "35") (pinfunction "SPARE5_35") (pintype "bidirectional"))
    )
    (net (code "22") (name "MOTOR_EN") (class "Default")
      (node (ref "R13") (pin "1") (pinfunction "1_1") (pintype "passive"))
      (node (ref "U$9") (pin "P$16") (pinfunction "P$16_P$16") (pintype "bidirectional"))
      (node (ref "U1") (pin "2") (pinfunction "EN2_2") (pintype "input"))
      (node (ref "U1") (pin "6") (pinfunction "EN1_6") (pintype "input"))
    )
    (net (code "23") (name "Net-(120-1)") (class "Default")
      (node (ref "120") (pin "P$1") (pinfunction "1_P$1") (pintype "passive"))
      (node (ref "C5") (pin "1") (pinfunction "1_1") (pintype "passive"))
      (node (ref "U$6") (pin "P$6") (pinfunction "VOUT_P$6") (pintype "bidirectional"))
    )
    (net (code "24") (name "Net-(CHARGING-PadC)") (class "Default")
      (node (ref "CHARGING") (pin "C") (pinfunction "C_C") (pintype "passive"))
      (node (ref "R14") (pin "2") (pinfunction "2_2") (pintype "passive"))
    )
    (net (code "25") (name "Net-(DISCHARGING-PadC)") (class "Default")
      (node (ref "DISCHARGING") (pin "C") (pinfunction "C_C") (pintype "passive"))
      (node (ref "R17") (pin "2") (pinfunction "2_2") (pintype "passive"))
    )
    (net (code "26") (name "Net-(POWER_IN-PadA)") (class "Default")
      (node (ref "POWER_IN") (pin "A") (pinfunction "A_A") (pintype "passive"))
      (node (ref "R20") (pin "1") (pinfunction "1_1") (pintype "passive"))
    )
    (net (code "27") (name "Net-(Q2-D)") (class "Default")
      (node (ref "Q2") (pin "3") (pinfunction "D_3") (pintype "bidirectional"))
      (node (ref "R44") (pin "1") (pinfunction "1_1") (pintype "passive"))
    )
    (net (code "28") (name "Net-(Q3-D)") (class "Default")
      (node (ref "Q3") (pin "3") (pinfunction "D_3") (pintype "bidirectional"))
      (node (ref "R12") (pin "1") (pinfunction "1_1") (pintype "passive"))
    )
    (net (code "29") (name "Net-(Q6-G)") (class "Default")
      (node (ref "Q6") (pin "1") (pinfunction "G_1") (pintype "passive"))
      (node (ref "R12") (pin "2") (pinfunction "2_2") (pintype "passive"))
      (node (ref "R9") (pin "1") (pinfunction "1_1") (pintype "passive"))
    )
    (net (code "30") (name "Net-(Q18-G)") (class "Default")
      (node (ref "Q18") (pin "1") (pinfunction "G_1") (pintype "passive"))
      (node (ref "R43") (pin "1") (pinfunction "1_1") (pintype "passive"))
      (node (ref "R44") (pin "2") (pinfunction "2_2") (pintype "passive"))
    )
    (net (code "31") (name "Net-(Q19-G)") (class "Default")
      (node (ref "Q19") (pin "1") (pinfunction "G_1") (pintype "bidirectional"))
      (node (ref "R1") (pin "1") (pinfunction "1_1") (pintype "passive"))
    )
    (net (code "32") (name "Net-(Q19-S)") (class "Default")
      (node (ref "Q19") (pin "2") (pinfunction "S_2") (pintype "bidirectional"))
      (node (ref "Q20") (pin "1") (pinfunction "G_1") (pintype "bidirectional"))
      (node (ref "R5") (pin "1") (pinfunction "1_1") (pintype "passive"))
    )
    (net (code "33") (name "Net-(Q20-D)") (class "Default")
      (node (ref "Q20") (pin "3") (pinfunction "D_3") (pintype "bidirectional"))
      (node (ref "R2") (pin "2") (pinfunction "2_2") (pintype "passive"))
    )
    (net (code "34") (name "Net-(U$6-REMOTE)") (class "Default")
      (node (ref "R2") (pin "1") (pinfunction "1_1") (pintype "passive"))
      (node (ref "U$6") (pin "P$3") (pinfunction "REMOTE_P$3") (pintype "bidirectional"))
    )
    (net (code "35") (name "Net-(U1-CP1)") (class "Default")
      (node (ref "C18") (pin "2") (pinfunction "2_2") (pintype "passive"))
      (node (ref "U1") (pin "11") (pinfunction "CP1_11") (pintype "passive"))
    )
    (net (code "36") (name "Net-(U1-CP2)") (class "Default")
      (node (ref "C18") (pin "1") (pinfunction "1_1") (pintype "passive"))
      (node (ref "U1") (pin "12") (pinfunction "CP2_12") (pintype "passive"))
    )
    (net (code "37") (name "Net-(U1-SENSE)") (class "Default")
      (node (ref "R4") (pin "2") (pinfunction "2_2") (pintype "passive"))
      (node (ref "U1") (pin "8") (pinfunction "SENSE_8") (pintype "output"))
    )
    (net (code "38") (name "Net-(U1-VCP)") (class "Default")
      (node (ref "C16") (pin "1") (pinfunction "1_1") (pintype "passive"))
      (node (ref "U1") (pin "14") (pinfunction "VCP_14") (pintype "output"))
    )
    (net (code "39") (name "PWM_DRIVER1") (class "Default")
      (node (ref "R3") (pin "1") (pinfunction "1_1") (pintype "passive"))
      (node (ref "U$9") (pin "P$9") (pinfunction "P$9_P$9") (pintype "bidirectional"))
      (node (ref "U1") (pin "3") (pinfunction "IN1_3") (pintype "input"))
    )
    (net (code "40") (name "PWM_DRIVER2") (class "Default")
      (node (ref "R8") (pin "1") (pinfunction "1_1") (pintype "passive"))
      (node (ref "U$9") (pin "P$19") (pinfunction "P$19_P$19") (pintype "bidirectional"))
      (node (ref "U1") (pin "16") (pinfunction "IN2_16") (pintype "input"))
    )
    (net (code "41") (name "PWM_OUT1") (class "Default")
      (node (ref "CLAW_CONTROL") (pin "1") (pinfunction "1_1") (pintype "passive"))
      (node (ref "U1") (pin "7") (pinfunction "OUT1_7") (pintype "output"))
    )
    (net (code "42") (name "PWM_OUT2") (class "Default")
      (node (ref "CLAW_CONTROL") (pin "3") (pinfunction "3_3") (pintype "passive"))
      (node (ref "U1") (pin "10") (pinfunction "OUT2_10") (pintype "output"))
    )
    (net (code "43") (name "SCL") (class "Default")
      (node (ref "U$1") (pin "31") (pinfunction "BOARD_SCL_31") (pintype "bidirectional"))
      (node (ref "U$9") (pin "P$17") (pinfunction "P$17_P$17") (pintype "bidirectional"))
    )
    (net (code "44") (name "SDA") (class "Default")
      (node (ref "U$1") (pin "32") (pinfunction "BOARD_SDA_32") (pintype "bidirectional"))
      (node (ref "U$9") (pin "P$7") (pinfunction "P$7_P$7") (pintype "bidirectional"))
    )
    (net (code "45") (name "TORPEDO1") (class "Default")
      (node (ref "Q18") (pin "3") (pinfunction "D_3") (pintype "passive"))
      (node (ref "TORPEDO_CONNECTOR") (pin "1") (pinfunction "1_1") (pintype "passive"))
    )
    (net (code "46") (name "TORPEDO1_GATE") (class "Default")
      (node (ref "Q2") (pin "1") (pinfunction "G_1") (pintype "bidirectional"))
      (node (ref "R18") (pin "1") (pinfunction "1_1") (pintype "passive"))
      (node (ref "U$9") (pin "P$2") (pinfunction "P$2_P$2") (pintype "bidirectional"))
    )
    (net (code "47") (name "TORPEDO2") (class "Default")
      (node (ref "Q6") (pin "3") (pinfunction "D_3") (pintype "passive"))
      (node (ref "TORPEDO_CONNECTOR") (pin "2") (pinfunction "2_2") (pintype "passive"))
    )
    (net (code "48") (name "TORPEDO2_GATE") (class "Default")
      (node (ref "Q3") (pin "1") (pinfunction "G_1") (pintype "bidirectional"))
      (node (ref "R19") (pin "1") (pinfunction "1_1") (pintype "passive"))
      (node (ref "U$9") (pin "P$12") (pinfunction "P$12_P$12") (pintype "bidirectional"))
    )
    (net (code "49") (name "V+") (class "Default")
      (node (ref "POWER_INPUT") (pin "4") (pinfunction "4_4") (pintype "passive"))
      (node (ref "Q20") (pin "2") (pinfunction "S_2") (pintype "bidirectional"))
      (node (ref "R20") (pin "2") (pinfunction "2_2") (pintype "passive"))
      (node (ref "R5") (pin "2") (pinfunction "2_2") (pintype "passive"))
      (node (ref "U$6") (pin "P$2") (pinfunction "VIN_P$2") (pintype "bidirectional"))
    )
    (net (code "50") (name "V_DIV") (class "Default")
      (node (ref "R10") (pin "2") (pinfunction "2_2") (pintype "passive"))
      (node (ref "R11") (pin "1") (pinfunction "1_1") (pintype "passive"))
      (node (ref "U$9") (pin "P$8") (pinfunction "P$8_P$8") (pintype "bidirectional"))
    )
    (net (code "51") (name "unconnected-(CLAW_CONTROL-Pad2)") (class "Default")
      (node (ref "CLAW_CONTROL") (pin "2") (pinfunction "2_2") (pintype "passive"))
    )
    (net (code "52") (name "unconnected-(CLAW_CONTROL-Pad4)") (class "Default")
      (node (ref "CLAW_CONTROL") (pin "4") (pinfunction "4_4") (pintype "passive"))
    )
    (net (code "53") (name "unconnected-(TORPEDO_CONNECTOR-Pad3)") (class "Default")
      (node (ref "TORPEDO_CONNECTOR") (pin "3") (pinfunction "3_3") (pintype "passive"))
    )
    (net (code "54") (name "unconnected-(TORPEDO_CONNECTOR-Pad4)") (class "Default")
      (node (ref "TORPEDO_CONNECTOR") (pin "4") (pinfunction "4_4") (pintype "passive"))
    )
    (net (code "55") (name "unconnected-(U$1-3.3V_ON{slash}OFF-Pad14)") (class "Default")
      (node (ref "U$1") (pin "14") (pinfunction "3.3V_ON/OFF_14") (pintype "bidirectional"))
    )
    (net (code "56") (name "unconnected-(U$1-5V_ON_OFF-Pad15)") (class "Default")
      (node (ref "U$1") (pin "15") (pinfunction "5V_ON_OFF_15") (pintype "bidirectional"))
    )
    (net (code "57") (name "unconnected-(U$1-12V_ON{slash}OFF-Pad16)") (class "Default")
      (node (ref "U$1") (pin "16") (pinfunction "12V_ON/OFF_16") (pintype "bidirectional"))
    )
    (net (code "58") (name "unconnected-(U$1-ACOUSTIC_ON{slash}OFF-Pad17)") (class "Default")
      (node (ref "U$1") (pin "17") (pinfunction "ACOUSTIC_ON/OFF_17") (pintype "bidirectional"))
    )
    (net (code "59") (name "unconnected-(U$1-JETSON_ON{slash}OFF-Pad18)") (class "Default")
      (node (ref "U$1") (pin "18") (pinfunction "JETSON_ON/OFF_18") (pintype "bidirectional"))
    )
    (net (code "60") (name "unconnected-(U$1-KILL_SWITCH-Pad37)") (class "Default")
      (node (ref "U$1") (pin "37") (pinfunction "KILL_SWITCH_37") (pintype "output"))
    )
    (net (code "61") (name "unconnected-(U$1-MOBO_ON{slash}OFF-Pad19)") (class "Default")
      (node (ref "U$1") (pin "19") (pinfunction "MOBO_ON/OFF_19") (pintype "bidirectional"))
    )
    (net (code "62") (name "unconnected-(U$1-PWM_1-Pad20)") (class "Default")
      (node (ref "U$1") (pin "20") (pinfunction "PWM_1_20") (pintype "bidirectional"))
    )
    (net (code "63") (name "unconnected-(U$1-PWM_2-Pad21)") (class "Default")
      (node (ref "U$1") (pin "21") (pinfunction "PWM_2_21") (pintype "bidirectional"))
    )
    (net (code "64") (name "unconnected-(U$1-PWM_3-Pad22)") (class "Default")
      (node (ref "U$1") (pin "22") (pinfunction "PWM_3_22") (pintype "bidirectional"))
    )
    (net (code "65") (name "unconnected-(U$1-PWM_4-Pad23)") (class "Default")
      (node (ref "U$1") (pin "23") (pinfunction "PWM_4_23") (pintype "bidirectional"))
    )
    (net (code "66") (name "unconnected-(U$1-PWM_5-Pad24)") (class "Default")
      (node (ref "U$1") (pin "24") (pinfunction "PWM_5_24") (pintype "bidirectional"))
    )
    (net (code "67") (name "unconnected-(U$1-PWM_6-Pad25)") (class "Default")
      (node (ref "U$1") (pin "25") (pinfunction "PWM_6_25") (pintype "bidirectional"))
    )
    (net (code "68") (name "unconnected-(U$1-PWM_7-Pad26)") (class "Default")
      (node (ref "U$1") (pin "26") (pinfunction "PWM_7_26") (pintype "bidirectional"))
    )
    (net (code "69") (name "unconnected-(U$1-PWM_8-Pad27)") (class "Default")
      (node (ref "U$1") (pin "27") (pinfunction "PWM_8_27") (pintype "bidirectional"))
    )
    (net (code "70") (name "unconnected-(U$1-SENSOR_SCL-Pad29)") (class "Default")
      (node (ref "U$1") (pin "29") (pinfunction "SENSOR_SCL_29") (pintype "bidirectional"))
    )
    (net (code "71") (name "unconnected-(U$1-SENSOR_SDA-Pad30)") (class "Default")
      (node (ref "U$1") (pin "30") (pinfunction "SENSOR_SDA_30") (pintype "bidirectional"))
    )
    (net (code "72") (name "unconnected-(U$1-SPARE1-Pad7)") (class "Default")
      (node (ref "U$1") (pin "7") (pinfunction "SPARE1_7") (pintype "bidirectional"))
    )
    (net (code "73") (name "unconnected-(U$1-SPARE3-Pad33)") (class "Default")
      (node (ref "U$1") (pin "33") (pinfunction "SPARE3_33") (pintype "bidirectional"))
    )
    (net (code "74") (name "unconnected-(U$1-SPARE4-Pad34)") (class "Default")
      (node (ref "U$1") (pin "34") (pinfunction "SPARE4_34") (pintype "bidirectional"))
    )
    (net (code "75") (name "unconnected-(U$1-SPARE8-Pad50)") (class "Default")
      (node (ref "U$1") (pin "50") (pinfunction "SPARE8_50") (pintype "bidirectional"))
    )
    (net (code "76") (name "unconnected-(U$1-SWITCH_1-Pad38)") (class "Default")
      (node (ref "U$1") (pin "38") (pinfunction "SWITCH_1_38") (pintype "output"))
    )
    (net (code "77") (name "unconnected-(U$1-SWITCH_2-Pad39)") (class "Default")
      (node (ref "U$1") (pin "39") (pinfunction "SWITCH_2_39") (pintype "output"))
    )
    (net (code "78") (name "unconnected-(U$1-SWITCH_3-Pad40)") (class "Default")
      (node (ref "U$1") (pin "40") (pinfunction "SWITCH_3_40") (pintype "output"))
    )
    (net (code "79") (name "unconnected-(U$1-SWITCH_4-Pad41)") (class "Default")
      (node (ref "U$1") (pin "41") (pinfunction "SWITCH_4_41") (pintype "output"))
    )
    (net (code "80") (name "unconnected-(U$1-SWITCH_5-Pad42)") (class "Default")
      (node (ref "U$1") (pin "42") (pinfunction "SWITCH_5_42") (pintype "output"))
    )
    (net (code "81") (name "unconnected-(U$9-PadP$6)") (class "Default")
      (node (ref "U$9") (pin "P$6") (pinfunction "P$6_P$6") (pintype "bidirectional"))
    )
    (net (code "82") (name "unconnected-(U1-NFAULT-Pad1)") (class "Default")
      (node (ref "U1") (pin "1") (pinfunction "NFAULT_1") (pintype "output"))
    )
    (net (code "83") (name "unconnected-(U1-VPROPI-Pad15)") (class "Default")
      (node (ref "U1") (pin "15") (pinfunction "VPROPI_15") (pintype "output"))
    )
  )
)
